# SparkFun_BLEMate2.net
KiCad netlist of a schematic drawn in EAGLE
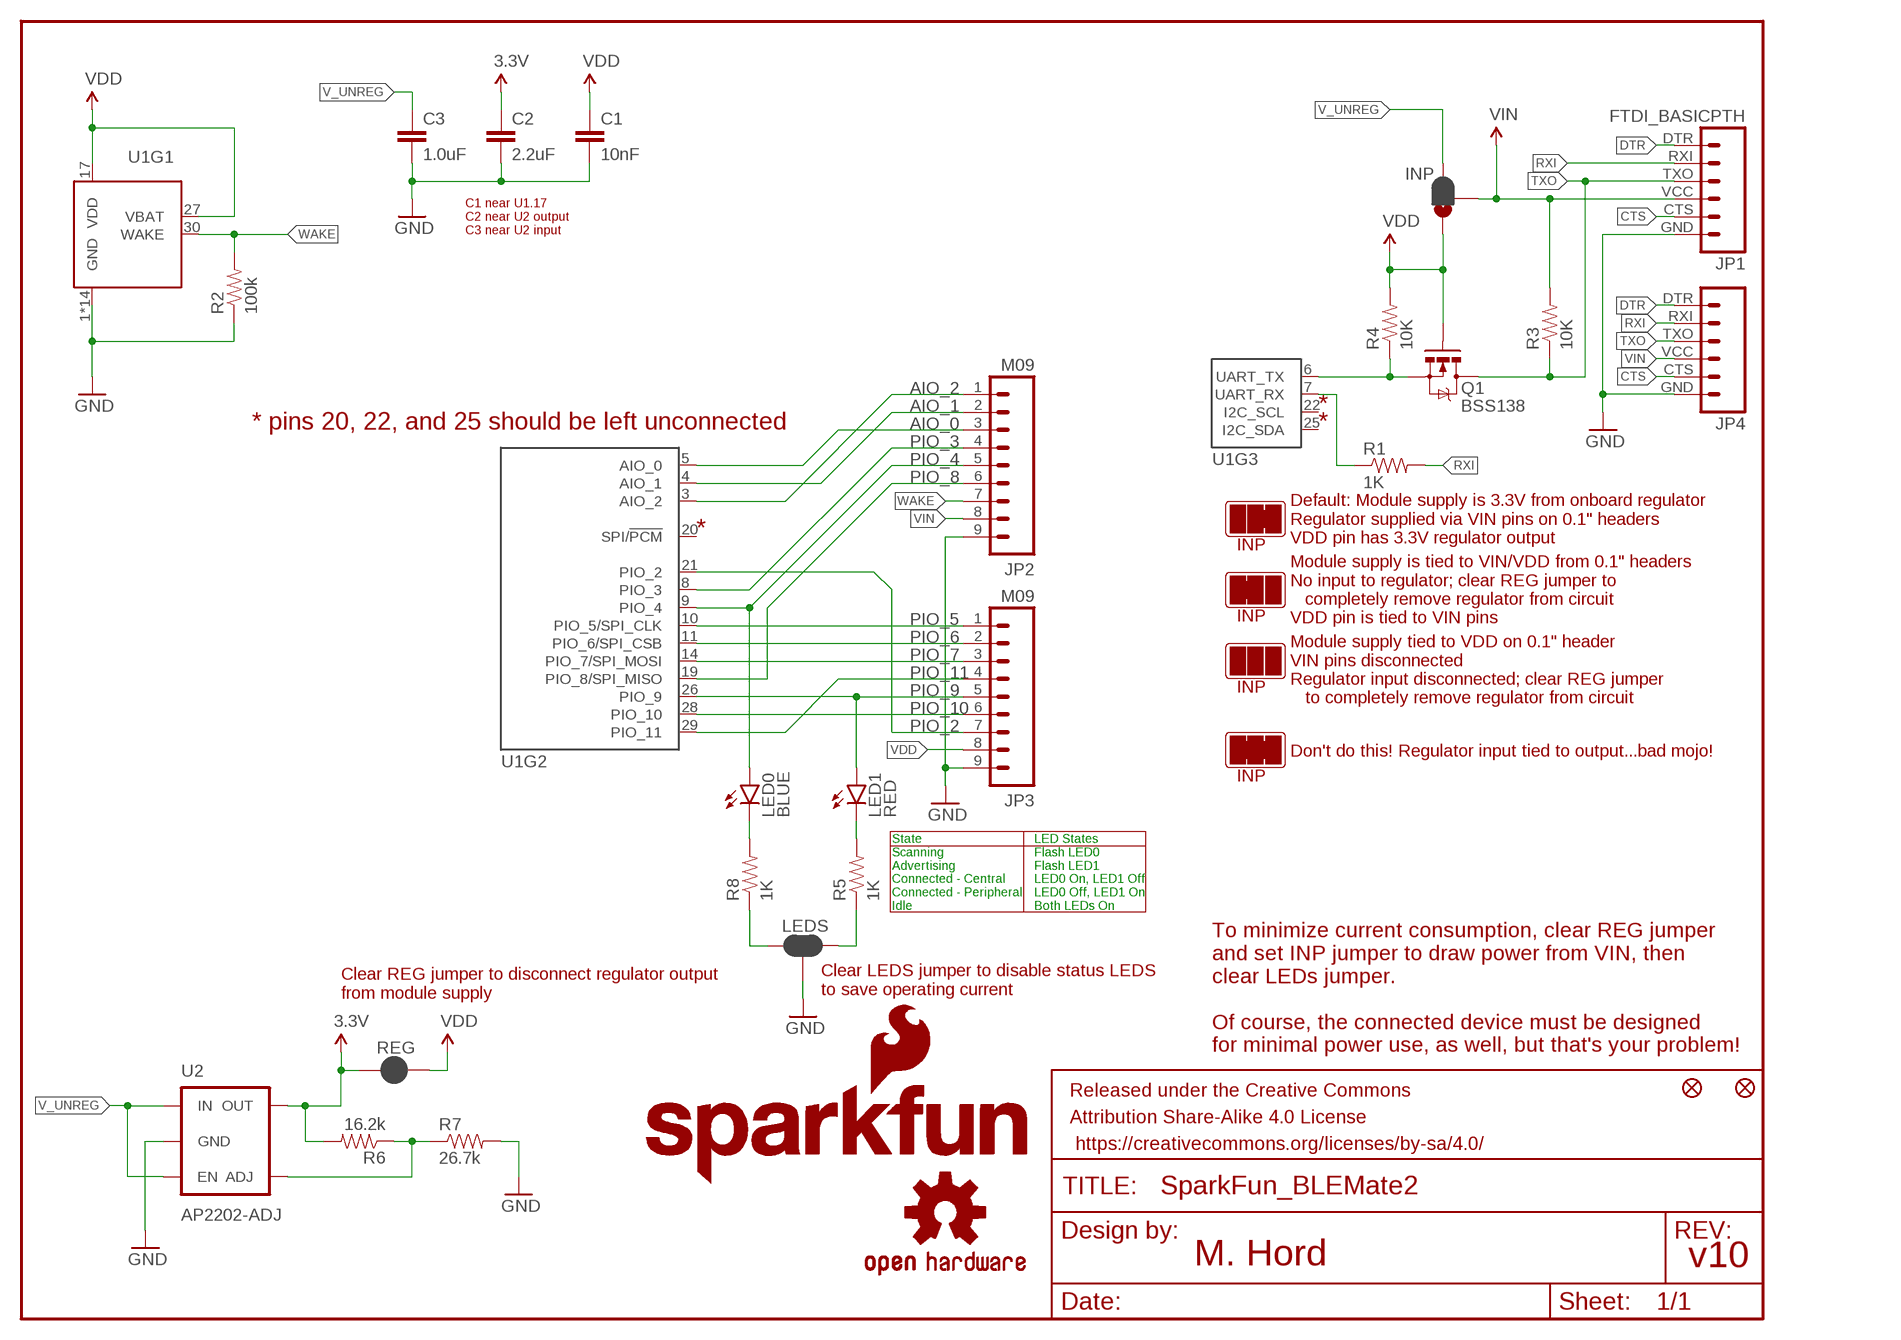
[diagram p0: schematic, sheet 1]

(export (version "E")
  (design (tool "Eeschema 10.0.6"))
  (components
    (comp (ref "C1")
      (value "10nF")
      (footprint "eagle-import:0603-CAP")
      (libsource (lib "eagle-import") (part "10NF/10000PF-50V-10%(0603)"))
    )
    (comp (ref "C2")
      (value "2.2uF")
      (footprint "eagle-import:0603-CAP")
      (libsource (lib "eagle-import") (part "2.2UF-10V-20%(0603)"))
    )
    (comp (ref "C3")
      (value "1.0uF")
      (footprint "eagle-import:0603-CAP")
      (libsource (lib "eagle-import") (part "1.0UF-16V-10%(0603)"))
    )
    (comp (ref "FID1")
      (value "FIDUCIAL1X2")
      (footprint "eagle-import:FIDUCIAL-1X2")
      (libsource (lib "eagle-import") (part "FIDUCIAL1X2"))
    )
    (comp (ref "FID2")
      (value "FIDUCIAL1X2")
      (footprint "eagle-import:FIDUCIAL-1X2")
      (libsource (lib "eagle-import") (part "FIDUCIAL1X2"))
    )
    (comp (ref "FRAME1")
      (value "FRAME-LETTER")
      (footprint "eagle-import:CREATIVE_COMMONS")
      (libsource (lib "eagle-import") (part "FRAME-LETTER"))
    )
    (comp (ref "INP")
      (value "JUMPER-PAD-3-2OF3_NC_BY_PASTE")
      (footprint "eagle-import:PAD-JUMPER-3-2OF3_NC_BY_PASTE_YES_SILK_FULL_BOX")
      (libsource (lib "eagle-import") (part "JUMPER-PAD-3-2OF3_NC_BY_PASTE"))
    )
    (comp (ref "JP1")
      (value "FTDI_BASICPTH")
      (footprint "eagle-import:FTDI_BASIC")
      (libsource (lib "eagle-import") (part "FTDI_BASICPTH"))
    )
    (comp (ref "JP2")
      (value "M09")
      (footprint "eagle-import:1X09")
      (libsource (lib "eagle-import") (part "M09"))
    )
    (comp (ref "JP3")
      (value "M09")
      (footprint "eagle-import:1X09")
      (libsource (lib "eagle-import") (part "M09"))
    )
    (comp (ref "JP4")
      (value "M06SIP")
      (footprint "eagle-import:1X06")
      (libsource (lib "eagle-import") (part "M06SIP"))
    )
    (comp (ref "LED0")
      (value "BLUE")
      (footprint "eagle-import:LED-0603")
      (libsource (lib "eagle-import") (part "LED-BLUE0603"))
    )
    (comp (ref "LED1")
      (value "RED")
      (footprint "eagle-import:LED-0603")
      (libsource (lib "eagle-import") (part "LED-RED0603"))
    )
    (comp (ref "LEDS")
      (value "JUMPER-PAD-3-NC_BY_PASTE")
      (footprint "eagle-import:PAD-JUMPER-3-NC_BY_PASTE_YES_SILK_FULL_BOX")
      (libsource (lib "eagle-import") (part "JUMPER-PAD-3-NC_BY_PASTE"))
    )
    (comp (ref "LOGO1")
      (value "SFE_LOGO_NAME.1_INCH")
      (footprint "eagle-import:SFE_LOGO_NAME_.1")
      (libsource (lib "eagle-import") (part "SFE_LOGO_NAME.1_INCH"))
    )
    (comp (ref "LOGO2")
      (value "OSHW-LOGOS")
      (footprint "eagle-import:OSHW-LOGO-S")
      (libsource (lib "eagle-import") (part "OSHW-LOGOS"))
    )
    (comp (ref "LOGO3")
      (value "SFE_LOGO_NAME_FLAME.1_INCH")
      (footprint "eagle-import:SFE_LOGO_NAME_FLAME_.1")
      (libsource (lib "eagle-import") (part "SFE_LOGO_NAME_FLAME.1_INCH"))
    )
    (comp (ref "LOGO4")
      (value "OSHW-LOGOS")
      (footprint "eagle-import:OSHW-LOGO-S")
      (libsource (lib "eagle-import") (part "OSHW-LOGOS"))
    )
    (comp (ref "Q1")
      (value "BSS138")
      (footprint "eagle-import:SOT23")
      (libsource (lib "eagle-import") (part "MOSFET-NCHANNELBSS138"))
    )
    (comp (ref "R1")
      (value "1K")
      (footprint "eagle-import:0603-RES")
      (libsource (lib "eagle-import") (part "1KOHM1/10W1%(0603)"))
    )
    (comp (ref "R2")
      (value "100k")
      (footprint "eagle-import:0603-RES")
      (libsource (lib "eagle-import") (part "100KOHM1/10W1%(0603)"))
    )
    (comp (ref "R3")
      (value "10K")
      (footprint "eagle-import:0603-RES")
      (libsource (lib "eagle-import") (part "10KOHM1/10W1%(0603)0603"))
    )
    (comp (ref "R4")
      (value "10K")
      (footprint "eagle-import:0603-RES")
      (libsource (lib "eagle-import") (part "10KOHM1/10W1%(0603)0603"))
    )
    (comp (ref "R5")
      (value "1K")
      (footprint "eagle-import:0603-RES")
      (libsource (lib "eagle-import") (part "1KOHM1/10W1%(0603)"))
    )
    (comp (ref "R6")
      (value "16.2k")
      (footprint "eagle-import:0603-RES")
      (libsource (lib "eagle-import") (part "16.2KOHM1/10W1%(0603)"))
    )
    (comp (ref "R7")
      (value "26.7k")
      (footprint "eagle-import:0603-RES")
      (libsource (lib "eagle-import") (part "16.2KOHM1/10W1%(0603)"))
    )
    (comp (ref "R8")
      (value "1K")
      (footprint "eagle-import:0603-RES")
      (libsource (lib "eagle-import") (part "1KOHM1/10W1%(0603)"))
    )
    (comp (ref "REG")
      (value "JUMPER-PAD-2-NC_BY_PASTE")
      (footprint "eagle-import:PAD-JUMPER-2-NC_BY_PASTE_YES_SILK")
      (libsource (lib "eagle-import") (part "JUMPER-PAD-2-NC_BY_PASTE"))
    )
    (comp (ref "U1")
      (value "BC118")
      (footprint "eagle-import:BC118")
      (libsource (lib "eagle-import") (part "BC118"))
    )
    (comp (ref "U2")
      (value "AP2202-ADJ")
      (footprint "eagle-import:SOT23-5")
      (libsource (lib "eagle-import") (part "AP2202-ADJ"))
    )
  )
  (nets
    (net (code "1") (name "/AIO_0") (class "Default")
      (node (ref "JP2") (pin "3") (pinfunction "3_3") (pintype "passive"))
      (node (ref "U1") (pin "5") (pinfunction "AIO_0_5") (pintype "bidirectional"))
    )
    (net (code "2") (name "/AIO_1") (class "Default")
      (node (ref "JP2") (pin "2") (pinfunction "2_2") (pintype "passive"))
      (node (ref "U1") (pin "4") (pinfunction "AIO_1_4") (pintype "bidirectional"))
    )
    (net (code "3") (name "/AIO_2") (class "Default")
      (node (ref "JP2") (pin "1") (pinfunction "1_1") (pintype "passive"))
      (node (ref "U1") (pin "3") (pinfunction "AIO_2_3") (pintype "bidirectional"))
    )
    (net (code "4") (name "/PIO_2") (class "Default")
      (node (ref "JP3") (pin "7") (pinfunction "7_7") (pintype "passive"))
      (node (ref "U1") (pin "21") (pinfunction "PIO_2_21") (pintype "bidirectional"))
    )
    (net (code "5") (name "/PIO_3") (class "Default")
      (node (ref "JP2") (pin "4") (pinfunction "4_4") (pintype "passive"))
      (node (ref "U1") (pin "8") (pinfunction "PIO_3_8") (pintype "bidirectional"))
    )
    (net (code "6") (name "/PIO_4") (class "Default")
      (node (ref "JP2") (pin "5") (pinfunction "5_5") (pintype "passive"))
      (node (ref "LED0") (pin "A") (pinfunction "A_A") (pintype "passive"))
      (node (ref "U1") (pin "9") (pinfunction "PIO_4_9") (pintype "bidirectional"))
    )
    (net (code "7") (name "/PIO_5") (class "Default")
      (node (ref "JP3") (pin "1") (pinfunction "1_1") (pintype "passive"))
      (node (ref "U1") (pin "10") (pinfunction "PIO_5/SPI_CLK_10") (pintype "bidirectional"))
    )
    (net (code "8") (name "/PIO_6") (class "Default")
      (node (ref "JP3") (pin "2") (pinfunction "2_2") (pintype "passive"))
      (node (ref "U1") (pin "11") (pinfunction "PIO_6/SPI_CSB_11") (pintype "bidirectional"))
    )
    (net (code "9") (name "/PIO_7") (class "Default")
      (node (ref "JP3") (pin "3") (pinfunction "3_3") (pintype "passive"))
      (node (ref "U1") (pin "14") (pinfunction "PIO_7/SPI_MOSI_14") (pintype "bidirectional"))
    )
    (net (code "10") (name "/PIO_8") (class "Default")
      (node (ref "JP2") (pin "6") (pinfunction "6_6") (pintype "passive"))
      (node (ref "U1") (pin "19") (pinfunction "PIO_8/SPI_MISO_19") (pintype "bidirectional"))
    )
    (net (code "11") (name "/PIO_9") (class "Default")
      (node (ref "JP3") (pin "5") (pinfunction "5_5") (pintype "passive"))
      (node (ref "LED1") (pin "A") (pinfunction "A_A") (pintype "passive"))
      (node (ref "U1") (pin "26") (pinfunction "PIO_9_26") (pintype "bidirectional"))
    )
    (net (code "12") (name "/PIO_10") (class "Default")
      (node (ref "JP3") (pin "6") (pinfunction "6_6") (pintype "passive"))
      (node (ref "U1") (pin "28") (pinfunction "PIO_10_28") (pintype "bidirectional"))
    )
    (net (code "13") (name "/PIO_11") (class "Default")
      (node (ref "JP3") (pin "4") (pinfunction "4_4") (pintype "passive"))
      (node (ref "U1") (pin "29") (pinfunction "PIO_11_29") (pintype "bidirectional"))
    )
    (net (code "14") (name "3.3V") (class "Default")
      (node (ref "C2") (pin "1") (pinfunction "1_1") (pintype "passive"))
      (node (ref "R6") (pin "2") (pinfunction "2_2") (pintype "passive"))
      (node (ref "REG") (pin "1") (pinfunction "1_1") (pintype "passive"))
      (node (ref "U2") (pin "5") (pinfunction "OUT_5") (pintype "passive"))
    )
    (net (code "15") (name "CTS") (class "Default")
      (node (ref "JP1") (pin "CTS") (pinfunction "5_CTS") (pintype "passive"))
      (node (ref "JP4") (pin "CTS") (pinfunction "5_CTS") (pintype "passive"))
    )
    (net (code "16") (name "DTR") (class "Default")
      (node (ref "JP1") (pin "DTR") (pinfunction "1_DTR") (pintype "passive"))
      (node (ref "JP4") (pin "DTR") (pinfunction "1_DTR") (pintype "passive"))
    )
    (net (code "17") (name "GND") (class "Default")
      (node (ref "C1") (pin "2") (pinfunction "2_2") (pintype "passive"))
      (node (ref "C2") (pin "2") (pinfunction "2_2") (pintype "passive"))
      (node (ref "C3") (pin "2") (pinfunction "2_2") (pintype "passive"))
      (node (ref "JP1") (pin "GND") (pinfunction "6_GND") (pintype "passive"))
      (node (ref "JP2") (pin "9") (pinfunction "9_9") (pintype "passive"))
      (node (ref "JP3") (pin "9") (pinfunction "9_9") (pintype "passive"))
      (node (ref "JP4") (pin "GND") (pinfunction "6_GND") (pintype "passive"))
      (node (ref "LEDS") (pin "2") (pinfunction "2_2") (pintype "passive"))
      (node (ref "R2") (pin "1") (pinfunction "1_1") (pintype "passive"))
      (node (ref "R7") (pin "2") (pinfunction "2_2") (pintype "passive"))
      (node (ref "U1") (pin "1") (pinfunction "GND_1") (pintype "bidirectional"))
      (node (ref "U1") (pin "12") (pinfunction "GND_12") (pintype "bidirectional"))
      (node (ref "U1") (pin "13") (pinfunction "GND_13") (pintype "bidirectional"))
      (node (ref "U1") (pin "15") (pinfunction "GND_15") (pintype "bidirectional"))
      (node (ref "U1") (pin "16") (pinfunction "GND_16") (pintype "bidirectional"))
      (node (ref "U1") (pin "18") (pinfunction "GND_18") (pintype "bidirectional"))
      (node (ref "U1") (pin "2") (pinfunction "GND_2") (pintype "bidirectional"))
      (node (ref "U1") (pin "23") (pinfunction "GND_23") (pintype "bidirectional"))
      (node (ref "U1") (pin "24") (pinfunction "GND_24") (pintype "bidirectional"))
      (node (ref "U1") (pin "31") (pinfunction "GND_31") (pintype "bidirectional"))
      (node (ref "U1") (pin "32") (pinfunction "GND_32") (pintype "bidirectional"))
      (node (ref "U1") (pin "33") (pinfunction "GND_33") (pintype "bidirectional"))
      (node (ref "U1") (pin "34") (pinfunction "GND_34") (pintype "bidirectional"))
      (node (ref "U1") (pin "35") (pinfunction "GND_35") (pintype "bidirectional"))
      (node (ref "U2") (pin "2") (pinfunction "GND_2") (pintype "input"))
    )
    (net (code "18") (name "Net-(LED0-PadC)") (class "Default")
      (node (ref "LED0") (pin "C") (pinfunction "C_C") (pintype "passive"))
      (node (ref "R8") (pin "2") (pinfunction "2_2") (pintype "passive"))
    )
    (net (code "19") (name "Net-(LED1-PadC)") (class "Default")
      (node (ref "LED1") (pin "C") (pinfunction "C_C") (pintype "passive"))
      (node (ref "R5") (pin "2") (pinfunction "2_2") (pintype "passive"))
    )
    (net (code "20") (name "Net-(LEDS-Pad1)") (class "Default")
      (node (ref "LEDS") (pin "1") (pinfunction "1_1") (pintype "passive"))
      (node (ref "R8") (pin "1") (pinfunction "1_1") (pintype "passive"))
    )
    (net (code "21") (name "Net-(LEDS-Pad3)") (class "Default")
      (node (ref "LEDS") (pin "3") (pinfunction "3_3") (pintype "passive"))
      (node (ref "R5") (pin "1") (pinfunction "1_1") (pintype "passive"))
    )
    (net (code "22") (name "Net-(Q1-S)") (class "Default")
      (node (ref "Q1") (pin "2") (pinfunction "S_2") (pintype "passive"))
      (node (ref "R4") (pin "1") (pinfunction "1_1") (pintype "passive"))
      (node (ref "U1") (pin "6") (pinfunction "UART_TX_6") (pintype "bidirectional"))
    )
    (net (code "23") (name "Net-(U1C-UART_RX)") (class "Default")
      (node (ref "R1") (pin "1") (pinfunction "1_1") (pintype "passive"))
      (node (ref "U1") (pin "7") (pinfunction "UART_RX_7") (pintype "bidirectional"))
    )
    (net (code "24") (name "Net-(U2-ADJ)") (class "Default")
      (node (ref "R6") (pin "1") (pinfunction "1_1") (pintype "passive"))
      (node (ref "R7") (pin "1") (pinfunction "1_1") (pintype "passive"))
      (node (ref "U2") (pin "4") (pinfunction "ADJ_4") (pintype "input"))
    )
    (net (code "25") (name "RXI") (class "Default")
      (node (ref "JP1") (pin "RXI") (pinfunction "2_RXI") (pintype "passive"))
      (node (ref "JP4") (pin "RXI") (pinfunction "2_RXI") (pintype "passive"))
      (node (ref "R1") (pin "2") (pinfunction "2_2") (pintype "passive"))
    )
    (net (code "26") (name "TXO") (class "Default")
      (node (ref "JP1") (pin "TXO") (pinfunction "3_TXO") (pintype "passive"))
      (node (ref "JP4") (pin "TXO") (pinfunction "3_TXO") (pintype "passive"))
      (node (ref "Q1") (pin "3") (pinfunction "D_3") (pintype "passive"))
      (node (ref "R3") (pin "1") (pinfunction "1_1") (pintype "passive"))
    )
    (net (code "27") (name "VDD") (class "Default")
      (node (ref "C1") (pin "1") (pinfunction "1_1") (pintype "passive"))
      (node (ref "INP") (pin "1") (pinfunction "1_1") (pintype "passive"))
      (node (ref "JP3") (pin "8") (pinfunction "8_8") (pintype "passive"))
      (node (ref "Q1") (pin "1") (pinfunction "G_1") (pintype "passive"))
      (node (ref "R4") (pin "2") (pinfunction "2_2") (pintype "passive"))
      (node (ref "REG") (pin "2") (pinfunction "2_2") (pintype "passive"))
      (node (ref "U1") (pin "17") (pinfunction "VDD_17") (pintype "bidirectional"))
      (node (ref "U1") (pin "27") (pinfunction "VBAT_27") (pintype "bidirectional"))
    )
    (net (code "28") (name "VIN") (class "Default")
      (node (ref "INP") (pin "2") (pinfunction "2_2") (pintype "passive"))
      (node (ref "JP1") (pin "VCC") (pinfunction "4_VCC") (pintype "passive"))
      (node (ref "JP2") (pin "8") (pinfunction "8_8") (pintype "passive"))
      (node (ref "JP4") (pin "VCC") (pinfunction "4_VCC") (pintype "passive"))
      (node (ref "R3") (pin "2") (pinfunction "2_2") (pintype "passive"))
    )
    (net (code "29") (name "V_UNREG") (class "Default")
      (node (ref "C3") (pin "1") (pinfunction "1_1") (pintype "passive"))
      (node (ref "INP") (pin "3") (pinfunction "3_3") (pintype "passive"))
      (node (ref "U2") (pin "1") (pinfunction "IN_1") (pintype "input"))
      (node (ref "U2") (pin "3") (pinfunction "EN_3") (pintype "input"))
    )
    (net (code "30") (name "WAKE") (class "Default")
      (node (ref "JP2") (pin "7") (pinfunction "7_7") (pintype "passive"))
      (node (ref "R2") (pin "2") (pinfunction "2_2") (pintype "passive"))
      (node (ref "U1") (pin "30") (pinfunction "WAKE_30") (pintype "bidirectional"))
    )
    (net (code "31") (name "unconnected-(U1B-SPI{slash}~{PCM}-Pad20)") (class "Default")
      (node (ref "U1") (pin "20") (pinfunction "SPI/~{PCM}_20") (pintype "bidirectional"))
    )
    (net (code "32") (name "unconnected-(U1C-I2C_SCL-Pad22)") (class "Default")
      (node (ref "U1") (pin "22") (pinfunction "I2C_SCL_22") (pintype "bidirectional"))
    )
    (net (code "33") (name "unconnected-(U1C-I2C_SDA-Pad25)") (class "Default")
      (node (ref "U1") (pin "25") (pinfunction "I2C_SDA_25") (pintype "bidirectional"))
    )
  )
)
